# MCU_LDO.net
KiCad netlist of a schematic drawn in Altium Designer
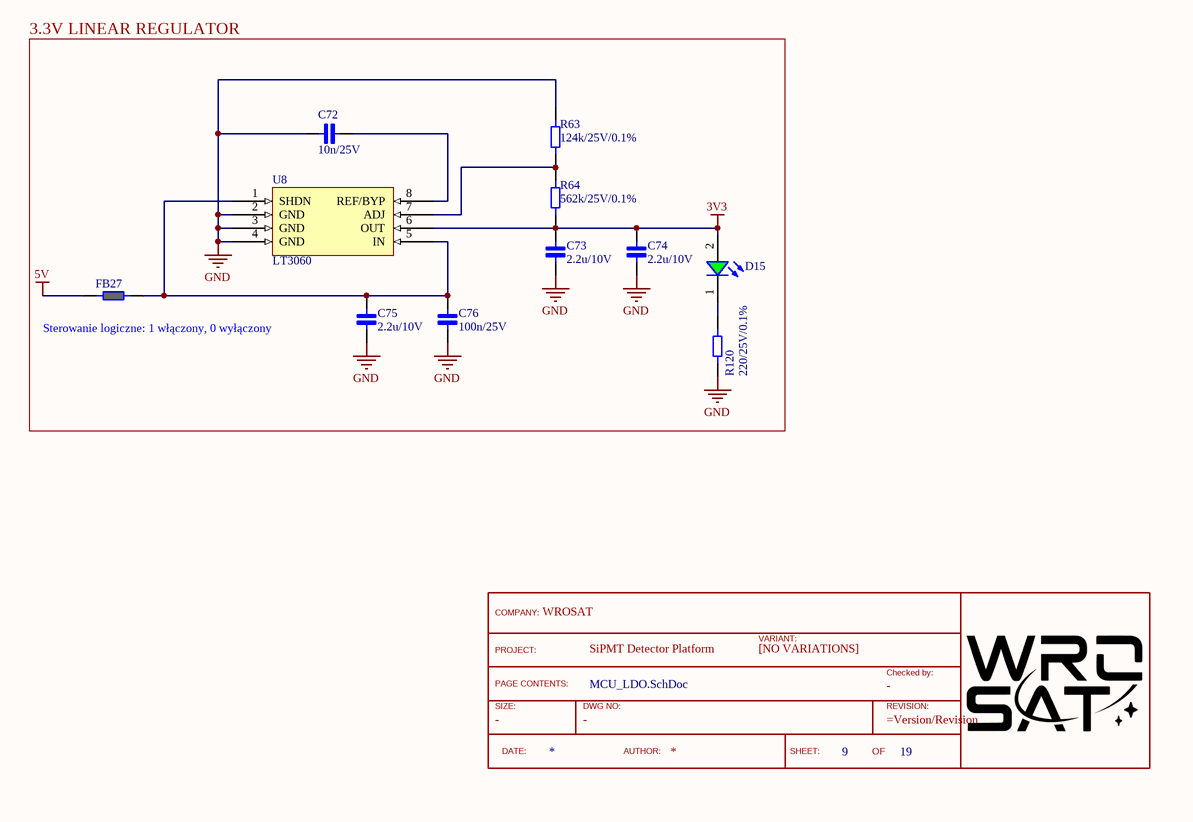
[diagram p0: MCU_LDO.SchDoc]

(export (version "E")
  (design (tool "Eeschema 10.0.6"))
  (components
    (comp (ref "C72")
      (value "10n/25V")
      (footprint "Cap_0402")
      (description "Ceramic Capacitor 10n / 0402 / 25V / ±5%, Wurth Elektronik MLCC")
      (libsource (lib "Cubesat_lib") (part "Cap_0402_10n"))
    )
    (comp (ref "C73")
      (value "2.2u/10V")
      (footprint "Cap_0402")
      (description "Ceramic Capacitor 2.2uF / 0402 / 10V / ±5%, Wurth Elektronik MLCC")
      (libsource (lib "Cubesat_lib") (part "Cap_0402_2.2u"))
    )
    (comp (ref "C74")
      (value "2.2u/10V")
      (footprint "Cap_0402")
      (description "Ceramic Capacitor 2.2uF / 0402 / 10V / ±5%, Wurth Elektronik MLCC")
      (libsource (lib "Cubesat_lib") (part "Cap_0402_2.2u"))
    )
    (comp (ref "C75")
      (value "2.2u/10V")
      (footprint "Cap_0402")
      (description "Ceramic Capacitor 2.2uF / 0402 / 10V / ±5%, Wurth Elektronik MLCC")
      (libsource (lib "Cubesat_lib") (part "Cap_0402_2.2u"))
    )
    (comp (ref "C76")
      (value "100n/25V")
      (footprint "Cap_0402")
      (description "Ceramic Capacitor 100n / 0402 / 25V / ±5%, Wurth Elektronik MLCC")
      (libsource (lib "Cubesat_lib") (part "Cap_0402_100n"))
    )
    (comp (ref "D15")
      (value "Green, 3.2V")
      (footprint "WL-SMCW_0603_H=0.7mm")
      (description "WL-SMCW SMT Mono-color Chip LED Waterclear, size 0603, Green, 3.2V, 140deg")
      (fields (field (name "PART NUMBER") "150060GS75000") (field (name "PUBLISHER") "Wurth Elektronik"))
      (libsource (lib "LEDS") (part "150060GS75000"))
    )
    (comp (ref "FB27")
      (value "Ferrite_bead_0402")
      (footprint "FERRITE_0402")
      (description "Ferrite bead, wurth 74269241102")
      (libsource (lib "Cubesat_lib") (part "Ferrite_bead_0402"))
    )
    (comp (ref "R63")
      (value "124k/25V/0.1%")
      (footprint "RES_0402")
      (description "Vishay, thin film resistor 124k/25V/0.1%")
      (libsource (lib "Cubesat_lib") (part "Res_0402_124k"))
    )
    (comp (ref "R64")
      (value "562k/25V/0.1%")
      (footprint "RES_0402")
      (description "Vishay, thin film resistor 562k/25V/0.1%")
      (libsource (lib "Cubesat_lib") (part "Res_0402_562k"))
    )
    (comp (ref "R120")
      (value "220/25V/0.1%")
      (footprint "RES_0402")
      (description "Vishay, thin film resistor 1/25V/0.1%")
      (libsource (lib "Cubesat_lib") (part "Res_0402_1"))
    )
    (comp (ref "U8")
      (value "LT3060")
      (footprint "TS8")
      (description "45V VIN, Micropower,\r\nLow Noise, 100mA Low\r\nDropout, Linear Regulator")
      (libsource (lib "Cubesat_lib") (part "Lt3060"))
    )
  )
  (nets
    (net (code "1") (name "3V3") (class "Default")
      (node (ref "C73") (pin "2") (pinfunction "2_2") (pintype "passive"))
      (node (ref "C74") (pin "2") (pinfunction "2_2") (pintype "passive"))
      (node (ref "D15") (pin "2") (pinfunction "A_2") (pintype "passive"))
      (node (ref "R64") (pin "1") (pinfunction "1_1") (pintype "passive"))
      (node (ref "U8") (pin "6") (pinfunction "OUT_6") (pintype "input"))
    )
    (net (code "2") (name "5V") (class "Default")
      (node (ref "FB27") (pin "1") (pinfunction "1_1") (pintype "passive"))
    )
    (net (code "3") (name "GND") (class "Default")
      (node (ref "C72") (pin "1") (pinfunction "1_1") (pintype "passive"))
      (node (ref "C73") (pin "1") (pinfunction "1_1") (pintype "passive"))
      (node (ref "C74") (pin "1") (pinfunction "1_1") (pintype "passive"))
      (node (ref "C75") (pin "1") (pinfunction "1_1") (pintype "passive"))
      (node (ref "C76") (pin "1") (pinfunction "1_1") (pintype "passive"))
      (node (ref "R120") (pin "1") (pinfunction "1_1") (pintype "passive"))
      (node (ref "R63") (pin "2") (pinfunction "2_2") (pintype "passive"))
      (node (ref "U8") (pin "2") (pinfunction "GND_2") (pintype "input"))
      (node (ref "U8") (pin "3") (pinfunction "GND_3") (pintype "input"))
      (node (ref "U8") (pin "4") (pinfunction "GND_4") (pintype "input"))
    )
    (net (code "4") (name "Net-(D15-K)") (class "Default")
      (node (ref "D15") (pin "1") (pinfunction "K_1") (pintype "passive"))
      (node (ref "R120") (pin "2") (pinfunction "2_2") (pintype "passive"))
    )
    (net (code "5") (name "Net-(U8-ADJ)") (class "Default")
      (node (ref "R63") (pin "1") (pinfunction "1_1") (pintype "passive"))
      (node (ref "R64") (pin "2") (pinfunction "2_2") (pintype "passive"))
      (node (ref "U8") (pin "7") (pinfunction "ADJ_7") (pintype "input"))
    )
    (net (code "6") (name "Net-(U8-IN)") (class "Default")
      (node (ref "C75") (pin "2") (pinfunction "2_2") (pintype "passive"))
      (node (ref "C76") (pin "2") (pinfunction "2_2") (pintype "passive"))
      (node (ref "FB27") (pin "2") (pinfunction "2_2") (pintype "passive"))
      (node (ref "U8") (pin "1") (pinfunction "SHDN_1") (pintype "input"))
      (node (ref "U8") (pin "5") (pinfunction "IN_5") (pintype "input"))
    )
    (net (code "7") (name "Net-(U8-REF{slash}BYP)") (class "Default")
      (node (ref "C72") (pin "2") (pinfunction "2_2") (pintype "passive"))
      (node (ref "U8") (pin "8") (pinfunction "REF/BYP_8") (pintype "input"))
    )
  )
)
